# 03_-_MAIN_SCHEMATIC.net
KiCad netlist of a schematic drawn in Altium Designer
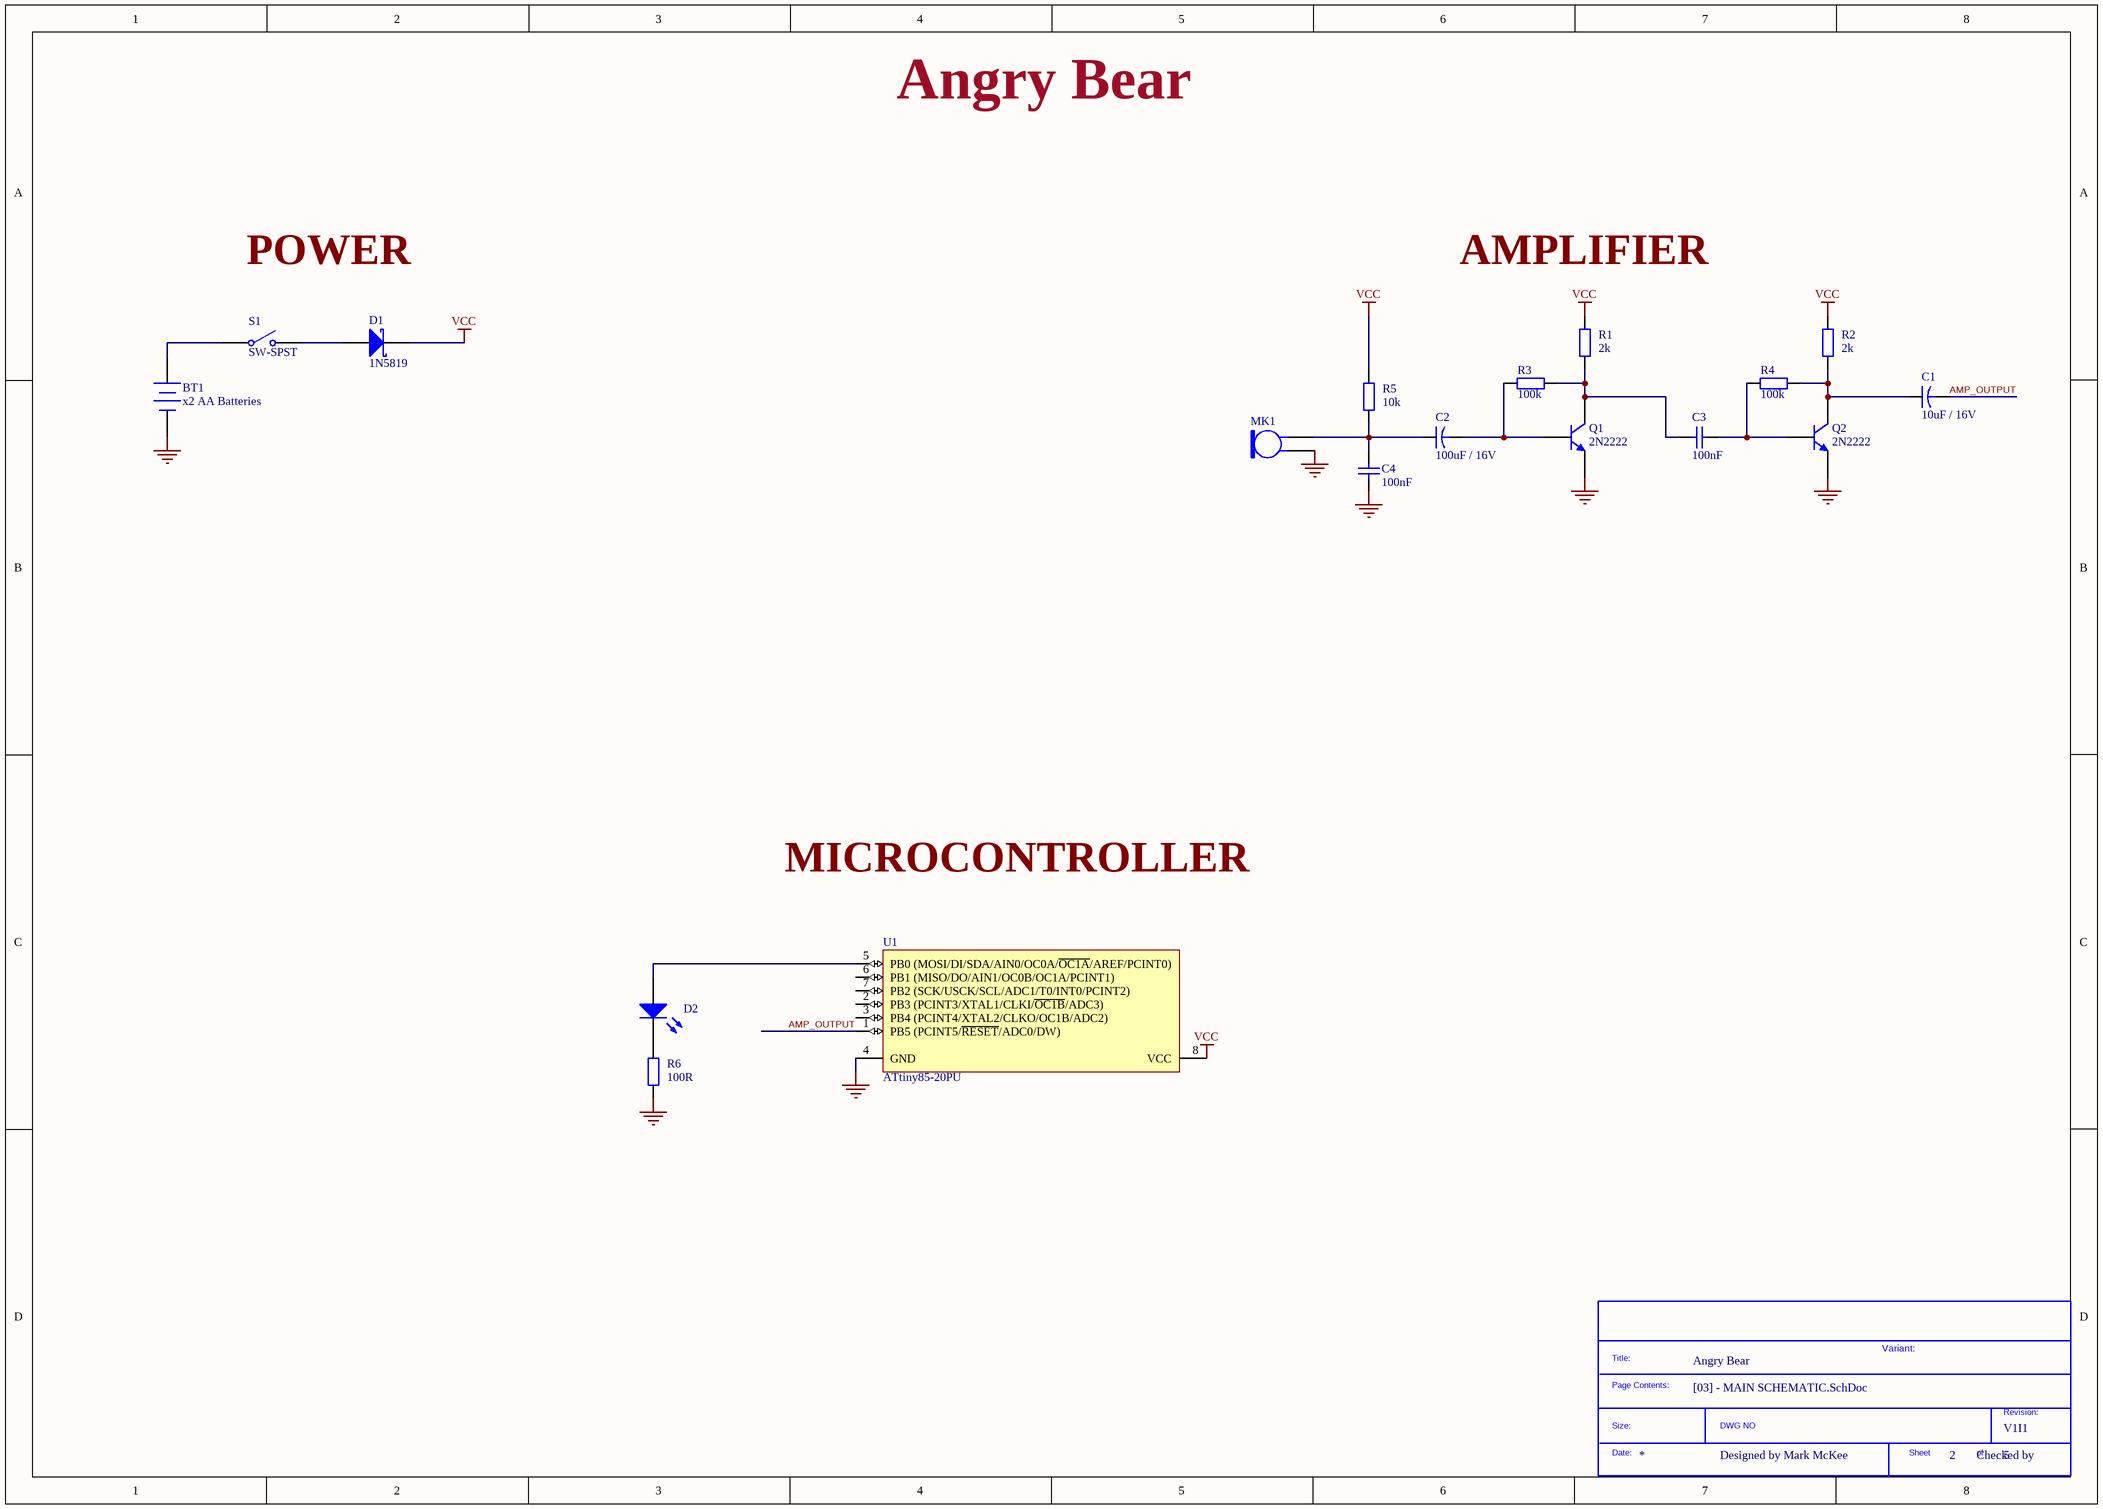
[diagram p0: [03] - MAIN SCHEMATIC.SchDoc]

(export (version "E")
  (design (tool "Eeschema 10.0.6"))
  (components
    (comp (ref "BT1")
      (value "x2 AA Batteries")
      (footprint "BAT-2")
      (description "Multicell Battery")
      (fields (field (name "PUBLISHER") "Altium Limited"))
      (libsource (lib "Miscellaneous Devices") (part "Battery"))
    )
    (comp (ref "C1")
      (value "10uF / 16V")
      (footprint "CAPR5-4X5")
      (description "Capacitor")
      (fields (field (name "PUBLISHER") "Altium Limited"))
      (libsource (lib "Miscellaneous Devices") (part "Cap2"))
    )
    (comp (ref "C2")
      (value "100uF / 16V")
      (footprint "CAPR5-4X5")
      (description "Capacitor")
      (fields (field (name "PUBLISHER") "Altium Limited"))
      (libsource (lib "Miscellaneous Devices") (part "Cap2"))
    )
    (comp (ref "C3")
      (value "100nF")
      (footprint "RAD-0.3")
      (description "Capacitor")
      (fields (field (name "PUBLISHER") "Altium Limited"))
      (libsource (lib "Miscellaneous Devices") (part "Cap"))
    )
    (comp (ref "C4")
      (value "100nF")
      (footprint "RAD-0.3")
      (description "Capacitor")
      (fields (field (name "PUBLISHER") "Altium Limited"))
      (libsource (lib "Miscellaneous Devices") (part "Cap"))
    )
    (comp (ref "D1")
      (value "1N5819")
      (footprint "DO-204AL")
      (description "Schottky Rectifier")
      (fields (field (name "PUBLISHER") "Altium Limited"))
      (libsource (lib "Miscellaneous Devices") (part "Diode 11DQ03"))
    )
    (comp (ref "D2")
      (value "LED0")
      (footprint "LED-0")
      (description "Typical INFRARED GaAs LED")
      (fields (field (name "PUBLISHER") "Altium Limited"))
      (libsource (lib "Miscellaneous Devices") (part "LED0"))
    )
    (comp (ref "MK1")
      (value "Mic2")
      (footprint "PIN2")
      (description "Microphone")
      (fields (field (name "PUBLISHER") "Altium Limited"))
      (libsource (lib "Miscellaneous Devices") (part "Mic2"))
    )
    (comp (ref "Q1")
      (value "2N2222")
      (footprint "TO-226-AA")
      (description "NPN Bipolar Transistor")
      (fields
        (field (name "MANUFACTURER") "ON Semiconductor")
        (field (name "MANUFACTURER PART NUMBER") "P2N2222AG")
        (field (name "PUBLISHER") "Altium Limited")
      )
      (libsource (lib "Miscellaneous Devices") (part "NPN"))
    )
    (comp (ref "Q2")
      (value "2N2222")
      (footprint "TO-226-AA")
      (description "NPN Bipolar Transistor")
      (fields
        (field (name "MANUFACTURER") "ON Semiconductor")
        (field (name "MANUFACTURER PART NUMBER") "P2N2222AG")
        (field (name "PUBLISHER") "Altium Limited")
      )
      (libsource (lib "Miscellaneous Devices") (part "NPN"))
    )
    (comp (ref "R1")
      (value "2k")
      (footprint "AXIAL-0.4")
      (description "Resistor")
      (fields (field (name "PUBLISHER") "Altium Limited"))
      (libsource (lib "") (part "Res2_1"))
    )
    (comp (ref "R2")
      (value "2k")
      (footprint "AXIAL-0.4")
      (description "Resistor")
      (fields (field (name "PUBLISHER") "Altium Limited"))
      (libsource (lib "") (part "Res2_1"))
    )
    (comp (ref "R3")
      (value "100k")
      (footprint "AXIAL-0.4")
      (description "Resistor")
      (fields (field (name "PUBLISHER") "Altium Limited"))
      (libsource (lib "Miscellaneous Devices") (part "Res2"))
    )
    (comp (ref "R4")
      (value "100k")
      (footprint "AXIAL-0.4")
      (description "Resistor")
      (fields (field (name "PUBLISHER") "Altium Limited"))
      (libsource (lib "Miscellaneous Devices") (part "Res2"))
    )
    (comp (ref "R5")
      (value "10k")
      (footprint "AXIAL-0.4")
      (description "Resistor")
      (fields (field (name "PUBLISHER") "Altium Limited"))
      (libsource (lib "") (part "Res2_1"))
    )
    (comp (ref "R6")
      (value "100R")
      (footprint "AXIAL-0.4")
      (description "Resistor")
      (fields (field (name "PUBLISHER") "Altium Limited"))
      (libsource (lib "") (part "Res2_1"))
    )
    (comp (ref "S1")
      (value "SW-SPST")
      (footprint "SPST-2")
      (description "Single-Pole, Single-Throw Switch")
      (fields (field (name "PUBLISHER") "Altium Limited"))
      (libsource (lib "Miscellaneous Devices") (part "SW-SPST"))
    )
    (comp (ref "U1")
      (value "ATtiny85-20PU")
      (footprint "8P3")
      (fields (field (name "PUBLISHER") "Altium Limited"))
      (libsource (lib "Atmel Microcontroller 8-Bit tinyAVR") (part "ATtiny85-20PU"))
    )
  )
  (nets
    (net (code "1") (name "/AMP_OUTPUT") (class "Default")
      (node (ref "C1") (pin "2") (pinfunction "2_2") (pintype "passive"))
      (node (ref "U1") (pin "1") (pinfunction "PB5_(PCINT5/~{RESET}/ADC0/DW)_1") (pintype "bidirectional"))
    )
    (net (code "2") (name "GND") (class "Default")
      (node (ref "BT1") (pin "2") (pinfunction "-_2") (pintype "passive"))
      (node (ref "C4") (pin "1") (pinfunction "1_1") (pintype "passive"))
      (node (ref "MK1") (pin "1") (pinfunction "1_1") (pintype "passive"))
      (node (ref "Q1") (pin "3") (pinfunction "E_3") (pintype "passive"))
      (node (ref "Q2") (pin "3") (pinfunction "E_3") (pintype "passive"))
      (node (ref "R6") (pin "1") (pinfunction "1_1") (pintype "passive"))
      (node (ref "U1") (pin "4") (pinfunction "GND_4") (pintype "power_in"))
    )
    (net (code "3") (name "Net-(BT1-+)") (class "Default")
      (node (ref "BT1") (pin "1") (pinfunction "+_1") (pintype "passive"))
      (node (ref "S1") (pin "1") (pinfunction "COMMON_1") (pintype "passive"))
    )
    (net (code "4") (name "Net-(C2-Pad1)") (class "Default")
      (node (ref "C2") (pin "1") (pinfunction "1_1") (pintype "passive"))
      (node (ref "C4") (pin "2") (pinfunction "2_2") (pintype "passive"))
      (node (ref "MK1") (pin "2") (pinfunction "2_2") (pintype "passive"))
      (node (ref "R5") (pin "1") (pinfunction "1_1") (pintype "passive"))
    )
    (net (code "5") (name "Net-(D1-A)") (class "Default")
      (node (ref "D1") (pin "1") (pinfunction "A_1") (pintype "passive"))
      (node (ref "S1") (pin "2") (pinfunction "NO_2") (pintype "passive"))
    )
    (net (code "6") (name "Net-(D2-A)") (class "Default")
      (node (ref "D2") (pin "1") (pinfunction "A_1") (pintype "passive"))
      (node (ref "U1") (pin "5") (pinfunction "PB0_(MOSI/DI/SDA/AIN0/OC0A/~{OC1A}/AREF/PCINT0)_5") (pintype "bidirectional"))
    )
    (net (code "7") (name "Net-(D2-K)") (class "Default")
      (node (ref "D2") (pin "2") (pinfunction "K_2") (pintype "passive"))
      (node (ref "R6") (pin "2") (pinfunction "2_2") (pintype "passive"))
    )
    (net (code "8") (name "Net-(Q1-B)") (class "Default")
      (node (ref "C2") (pin "2") (pinfunction "2_2") (pintype "passive"))
      (node (ref "Q1") (pin "2") (pinfunction "B_2") (pintype "passive"))
      (node (ref "R3") (pin "1") (pinfunction "1_1") (pintype "passive"))
    )
    (net (code "9") (name "Net-(Q1-C)") (class "Default")
      (node (ref "C3") (pin "1") (pinfunction "1_1") (pintype "passive"))
      (node (ref "Q1") (pin "1") (pinfunction "C_1") (pintype "passive"))
      (node (ref "R1") (pin "1") (pinfunction "1_1") (pintype "passive"))
      (node (ref "R3") (pin "2") (pinfunction "2_2") (pintype "passive"))
    )
    (net (code "10") (name "Net-(Q2-B)") (class "Default")
      (node (ref "C3") (pin "2") (pinfunction "2_2") (pintype "passive"))
      (node (ref "Q2") (pin "2") (pinfunction "B_2") (pintype "passive"))
      (node (ref "R4") (pin "1") (pinfunction "1_1") (pintype "passive"))
    )
    (net (code "11") (name "Net-(Q2-C)") (class "Default")
      (node (ref "C1") (pin "1") (pinfunction "1_1") (pintype "passive"))
      (node (ref "Q2") (pin "1") (pinfunction "C_1") (pintype "passive"))
      (node (ref "R2") (pin "1") (pinfunction "1_1") (pintype "passive"))
      (node (ref "R4") (pin "2") (pinfunction "2_2") (pintype "passive"))
    )
    (net (code "12") (name "VCC") (class "Default")
      (node (ref "D1") (pin "2") (pinfunction "K_2") (pintype "passive"))
      (node (ref "R1") (pin "2") (pinfunction "2_2") (pintype "passive"))
      (node (ref "R2") (pin "2") (pinfunction "2_2") (pintype "passive"))
      (node (ref "R5") (pin "2") (pinfunction "2_2") (pintype "passive"))
      (node (ref "U1") (pin "8") (pinfunction "VCC_8") (pintype "power_in"))
    )
    (net (code "13") (name "unconnected-(U1-PB1_(MISO{slash}DO{slash}AIN1{slash}OC0B{slash}OC1A{slash}PCINT1)-Pad6)") (class "Default")
      (node (ref "U1") (pin "6") (pinfunction "PB1_(MISO/DO/AIN1/OC0B/OC1A/PCINT1)_6") (pintype "bidirectional"))
    )
    (net (code "14") (name "unconnected-(U1-PB2_(SCK{slash}USCK{slash}SCL{slash}ADC1{slash}T0{slash}INT0{slash}PCINT2)-Pad7)") (class "Default")
      (node (ref "U1") (pin "7") (pinfunction "PB2_(SCK/USCK/SCL/ADC1/T0/INT0/PCINT2)_7") (pintype "bidirectional"))
    )
    (net (code "15") (name "unconnected-(U1-PB3_(PCINT3{slash}XTAL1{slash}CLKI{slash}~{OC1B}{slash}ADC3)-Pad2)") (class "Default")
      (node (ref "U1") (pin "2") (pinfunction "PB3_(PCINT3/XTAL1/CLKI/~{OC1B}/ADC3)_2") (pintype "bidirectional"))
    )
    (net (code "16") (name "unconnected-(U1-PB4_(PCINT4{slash}XTAL2{slash}CLKO{slash}OC1B{slash}ADC2)-Pad3)") (class "Default")
      (node (ref "U1") (pin "3") (pinfunction "PB4_(PCINT4/XTAL2/CLKO/OC1B/ADC2)_3") (pintype "bidirectional"))
    )
  )
)
